# trophy.net
KiCad netlist of a schematic drawn in EAGLE
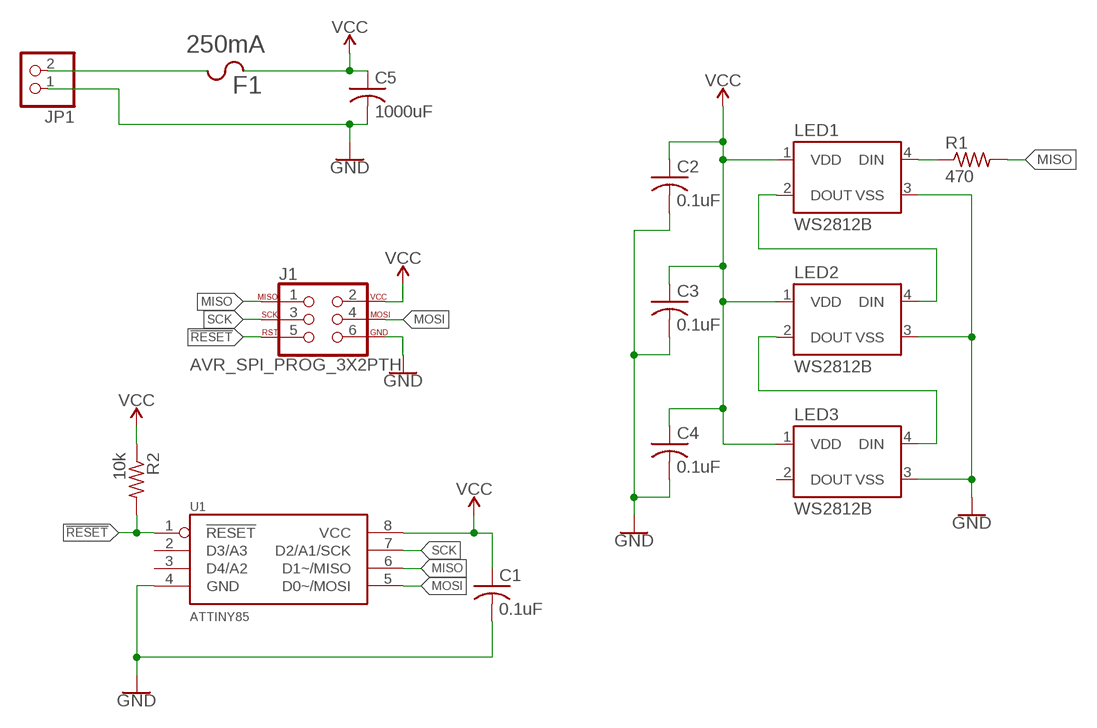
[diagram p0: schematic, sheet 1]

(export (version "E")
  (design (tool "Eeschema 10.0.6"))
  (components
    (comp (ref "C1")
      (value "0.1uF")
      (footprint "eagle-import:C0805")
      (libsource (lib "eagle-import") (part "C-USC0805"))
    )
    (comp (ref "C2")
      (value "0.1uF")
      (footprint "eagle-import:C0805")
      (libsource (lib "eagle-import") (part "C-USC0805"))
    )
    (comp (ref "C3")
      (value "0.1uF")
      (footprint "eagle-import:C0805")
      (libsource (lib "eagle-import") (part "C-USC0805"))
    )
    (comp (ref "C4")
      (value "0.1uF")
      (footprint "eagle-import:C0805")
      (libsource (lib "eagle-import") (part "C-USC0805"))
    )
    (comp (ref "C5")
      (value "1000uF")
      (footprint "eagle-import:CAP-3,5-8")
      (libsource (lib "eagle-import") (part "CAPACITOR"))
    )
    (comp (ref "F1")
      (value "250mA")
      (footprint "eagle-import:F1206")
      (libsource (lib "eagle-import") (part "FUSE"))
    )
    (comp (ref "J1")
      (value "AVR_SPI_PROG_3X2PTH")
      (footprint "eagle-import:2X3")
      (libsource (lib "eagle-import") (part "AVR_SPI_PROG_3X2PTH"))
    )
    (comp (ref "JP1")
      (value "PINHD-1X2")
      (footprint "eagle-import:1X02")
      (libsource (lib "eagle-import") (part "PINHD-1X2"))
    )
    (comp (ref "LED1")
      (value "WS2812B")
      (footprint "eagle-import:5050")
      (fields (field (name "MPN") "1655"))
      (libsource (lib "eagle-import") (part "WS2812B"))
    )
    (comp (ref "LED2")
      (value "WS2812B")
      (footprint "eagle-import:5050")
      (fields (field (name "MPN") "1655"))
      (libsource (lib "eagle-import") (part "WS2812B"))
    )
    (comp (ref "LED3")
      (value "WS2812B")
      (footprint "eagle-import:5050")
      (fields (field (name "MPN") "1655"))
      (libsource (lib "eagle-import") (part "WS2812B"))
    )
    (comp (ref "R1")
      (value "470")
      (footprint "eagle-import:R0805")
      (libsource (lib "eagle-import") (part "R-US_R0805"))
    )
    (comp (ref "R2")
      (value "10k")
      (footprint "eagle-import:R0805")
      (libsource (lib "eagle-import") (part "R-US_R0805"))
    )
    (comp (ref "U1")
      (value "ATTINY85")
      (footprint "eagle-import:8S2")
      (libsource (lib "eagle-import") (part "ATTINY85"))
    )
  )
  (nets
    (net (code "1") (name "/~{RESET}") (class "Default")
      (node (ref "J1") (pin "5") (pinfunction "5_5") (pintype "passive"))
      (node (ref "R2") (pin "2") (pinfunction "2_2") (pintype "passive"))
      (node (ref "U1") (pin "1") (pinfunction "~{RESET}_1") (pintype "input"))
    )
    (net (code "2") (name "GND") (class "Default")
      (node (ref "C1") (pin "2") (pinfunction "2_2") (pintype "passive"))
      (node (ref "C2") (pin "2") (pinfunction "2_2") (pintype "passive"))
      (node (ref "C3") (pin "2") (pinfunction "2_2") (pintype "passive"))
      (node (ref "C4") (pin "2") (pinfunction "2_2") (pintype "passive"))
      (node (ref "C5") (pin "NEGATIVE") (pinfunction "NEGATIVE_NEGATIVE") (pintype "passive"))
      (node (ref "J1") (pin "6") (pinfunction "6_6") (pintype "passive"))
      (node (ref "JP1") (pin "1") (pinfunction "1_1") (pintype "passive"))
      (node (ref "LED1") (pin "3") (pinfunction "VSS_3") (pintype "bidirectional"))
      (node (ref "LED2") (pin "3") (pinfunction "VSS_3") (pintype "bidirectional"))
      (node (ref "LED3") (pin "3") (pinfunction "VSS_3") (pintype "bidirectional"))
      (node (ref "U1") (pin "4") (pinfunction "GND_4") (pintype "power_in"))
    )
    (net (code "3") (name "MISO") (class "Default")
      (node (ref "J1") (pin "1") (pinfunction "1_1") (pintype "passive"))
      (node (ref "R1") (pin "2") (pinfunction "2_2") (pintype "passive"))
      (node (ref "U1") (pin "6") (pinfunction "D1~{/MISO}_6") (pintype "bidirectional"))
    )
    (net (code "4") (name "MOSI") (class "Default")
      (node (ref "J1") (pin "4") (pinfunction "4_4") (pintype "passive"))
      (node (ref "U1") (pin "5") (pinfunction "D0~{/MOSI}_5") (pintype "bidirectional"))
    )
    (net (code "5") (name "Net-(F1-Pad2)") (class "Default")
      (node (ref "F1") (pin "2") (pinfunction "2_2") (pintype "bidirectional"))
      (node (ref "JP1") (pin "2") (pinfunction "2_2") (pintype "passive"))
    )
    (net (code "6") (name "Net-(LED1-DIN)") (class "Default")
      (node (ref "LED1") (pin "4") (pinfunction "DIN_4") (pintype "bidirectional"))
      (node (ref "R1") (pin "1") (pinfunction "1_1") (pintype "passive"))
    )
    (net (code "7") (name "Net-(LED1-DOUT)") (class "Default")
      (node (ref "LED1") (pin "2") (pinfunction "DOUT_2") (pintype "bidirectional"))
      (node (ref "LED2") (pin "4") (pinfunction "DIN_4") (pintype "bidirectional"))
    )
    (net (code "8") (name "Net-(LED2-DOUT)") (class "Default")
      (node (ref "LED2") (pin "2") (pinfunction "DOUT_2") (pintype "bidirectional"))
      (node (ref "LED3") (pin "4") (pinfunction "DIN_4") (pintype "bidirectional"))
    )
    (net (code "9") (name "SCK") (class "Default")
      (node (ref "J1") (pin "3") (pinfunction "3_3") (pintype "passive"))
      (node (ref "U1") (pin "7") (pinfunction "D2/A1/SCK_7") (pintype "bidirectional"))
    )
    (net (code "10") (name "VCC") (class "Default")
      (node (ref "C1") (pin "1") (pinfunction "1_1") (pintype "passive"))
      (node (ref "C2") (pin "1") (pinfunction "1_1") (pintype "passive"))
      (node (ref "C3") (pin "1") (pinfunction "1_1") (pintype "passive"))
      (node (ref "C4") (pin "1") (pinfunction "1_1") (pintype "passive"))
      (node (ref "C5") (pin "POSITIVE") (pinfunction "POSITIVE_POSITIVE") (pintype "passive"))
      (node (ref "F1") (pin "1") (pinfunction "1_1") (pintype "bidirectional"))
      (node (ref "J1") (pin "2") (pinfunction "2_2") (pintype "passive"))
      (node (ref "LED1") (pin "1") (pinfunction "VDD_1") (pintype "bidirectional"))
      (node (ref "LED2") (pin "1") (pinfunction "VDD_1") (pintype "bidirectional"))
      (node (ref "LED3") (pin "1") (pinfunction "VDD_1") (pintype "bidirectional"))
      (node (ref "R2") (pin "1") (pinfunction "1_1") (pintype "passive"))
      (node (ref "U1") (pin "8") (pinfunction "VCC_8") (pintype "power_in"))
    )
    (net (code "11") (name "unconnected-(LED3-DOUT-Pad2)") (class "Default")
      (node (ref "LED3") (pin "2") (pinfunction "DOUT_2") (pintype "bidirectional"))
    )
    (net (code "12") (name "unconnected-(U1-D3{slash}A3-Pad2)") (class "Default")
      (node (ref "U1") (pin "2") (pinfunction "D3/A3_2") (pintype "bidirectional"))
    )
    (net (code "13") (name "unconnected-(U1-D4{slash}A2-Pad3)") (class "Default")
      (node (ref "U1") (pin "3") (pinfunction "D4/A2_3") (pintype "bidirectional"))
    )
  )
)
